# Derby_EDA.net
KiCad netlist of a schematic drawn in EasyEDA
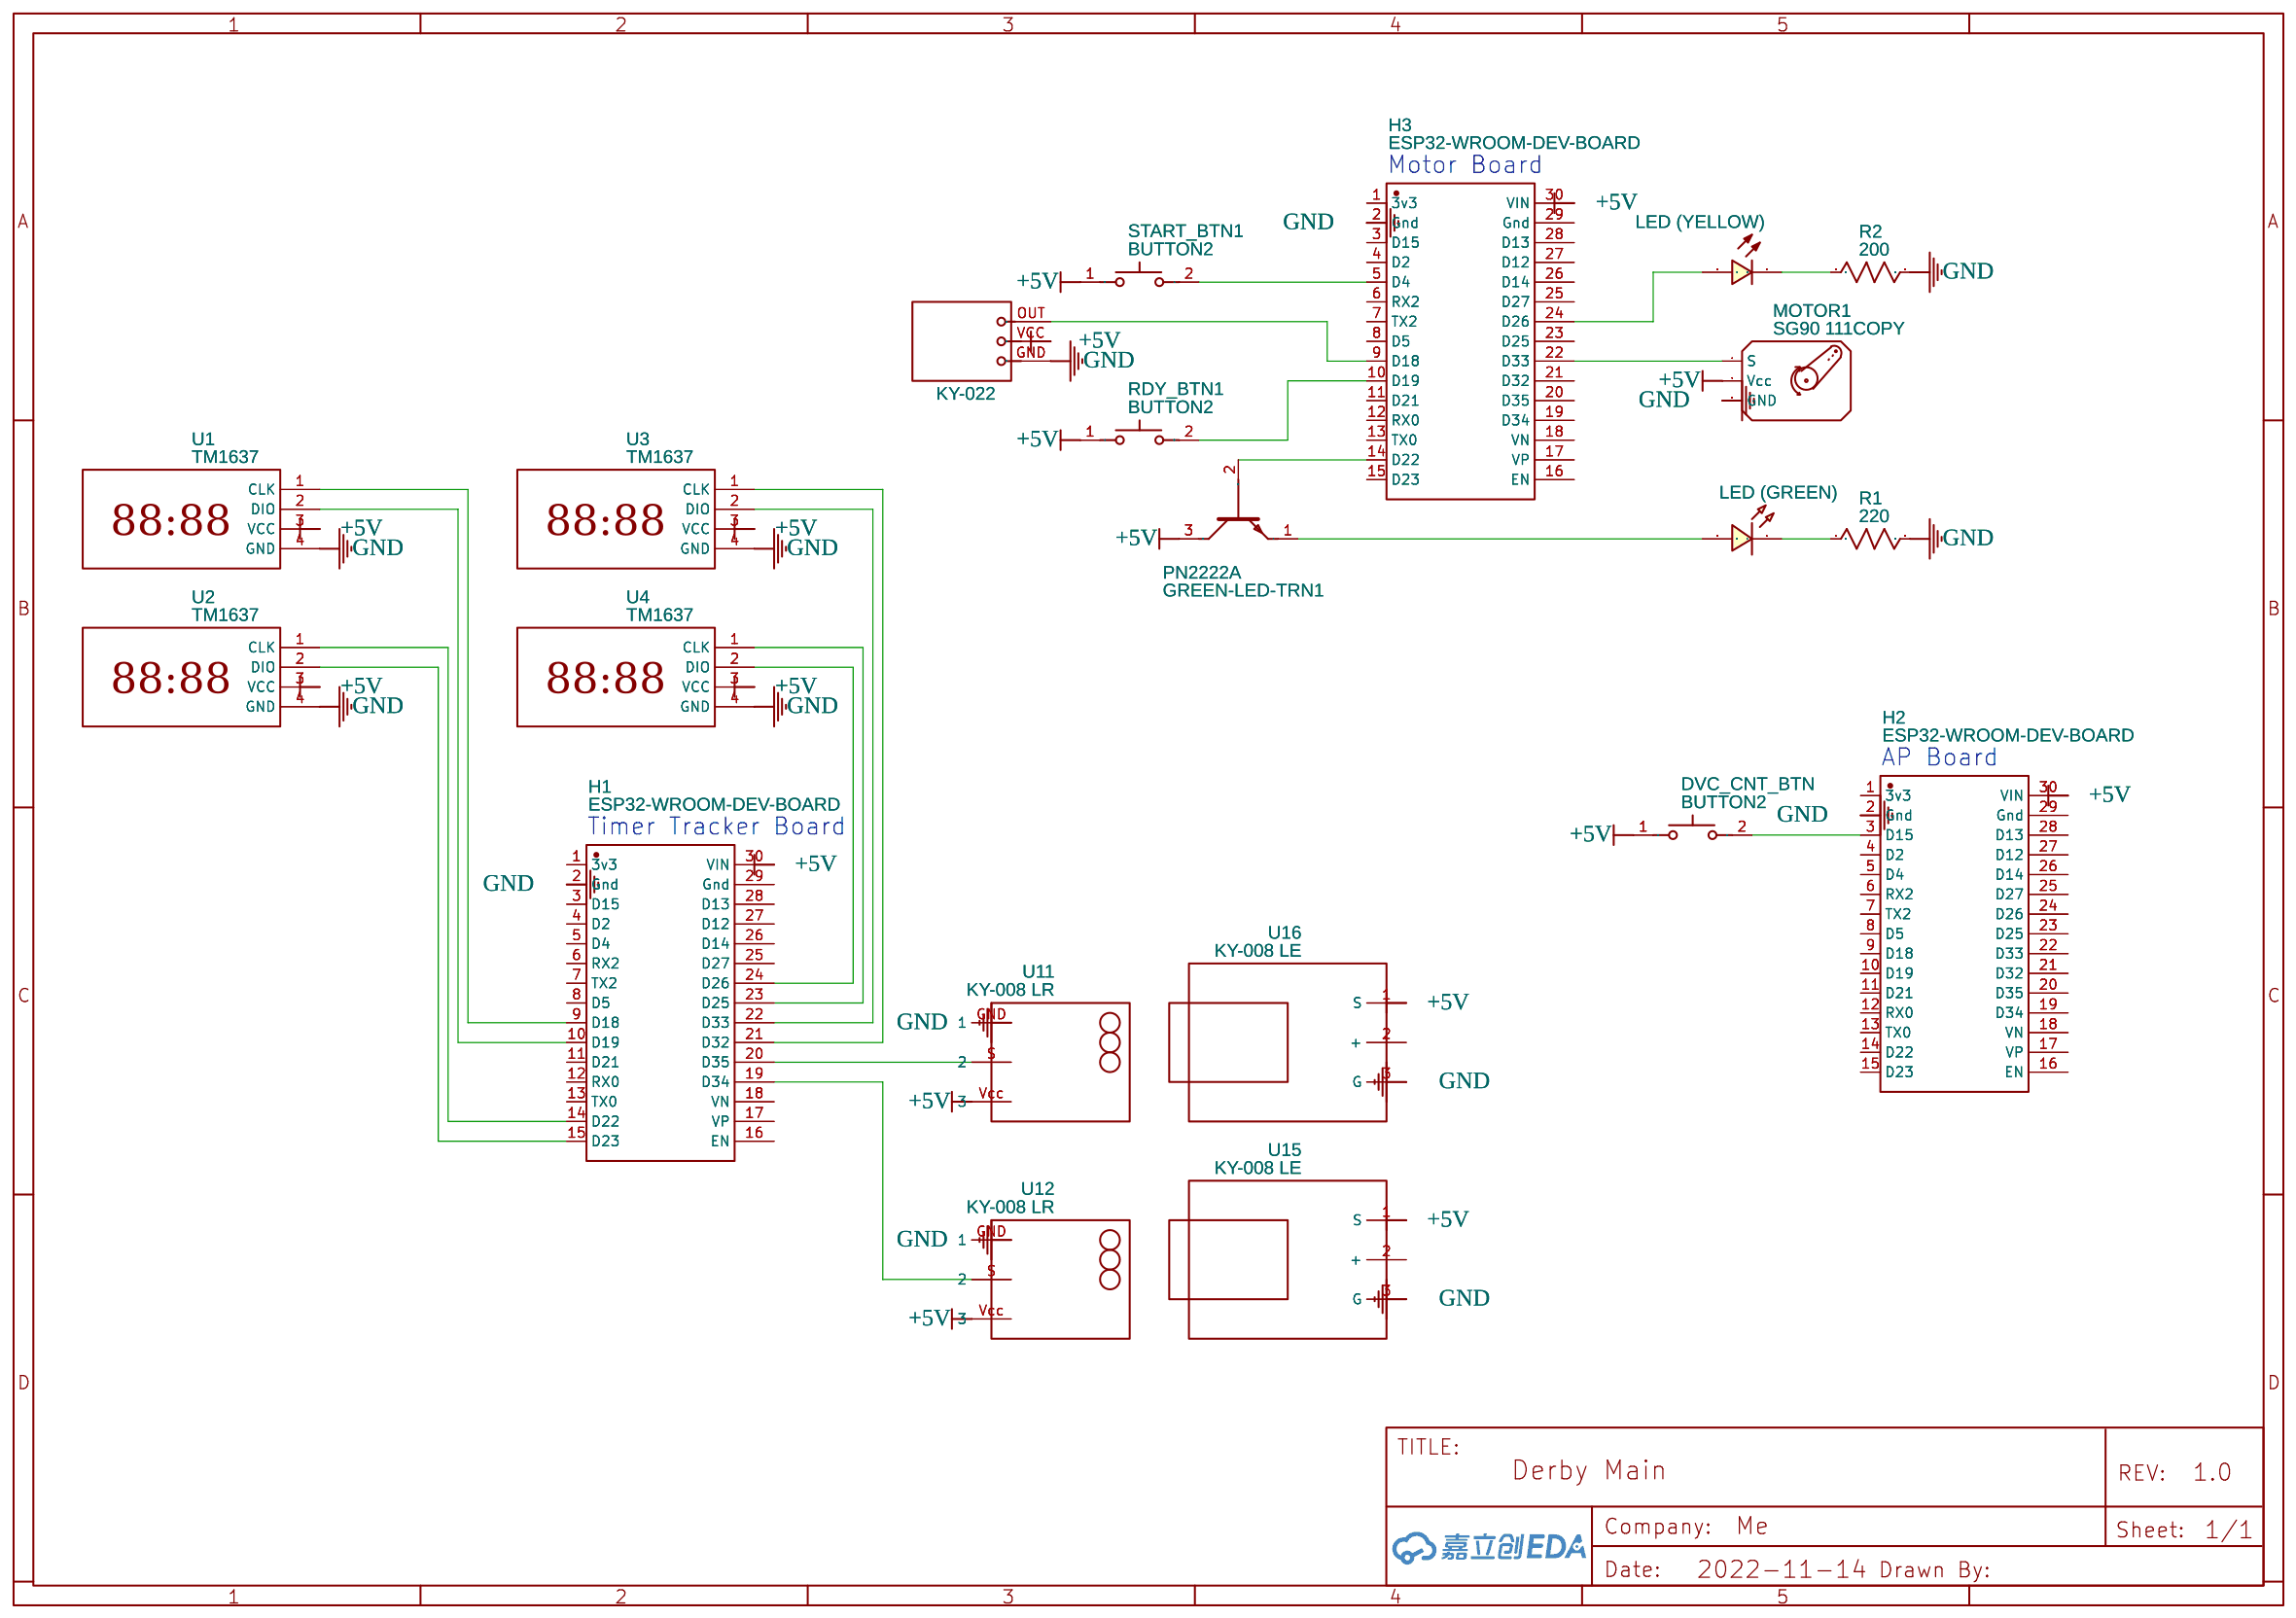
[diagram p0: schematic sheet]

(export (version "E")
  (design (tool "Eeschema 10.0.6"))
  (components
    (comp (ref "DVC_CNT_BTN")
      (value "BUTTON2")
      (fields (field (name "BOM_Supplier Part") "C9900005988"))
      (libsource (lib "") (part "BUTTON2_1"))
    )
    (comp (ref "GREEN-LED-TRN1") (value "PN2222A") (libsource (lib "") (part "PN2222A")))
    (comp (ref "H1")
      (value "ESP32-WROOM-DEV-BOARD")
      (fields
        (field (name "BOM_Manufacturer Part") "ESP32-WROOM-DEV")
        (field (name "BOM_Supplier Part") "ESP32")
      )
      (libsource (lib "") (part "ESP32-WROOM-DEV-BOARD"))
    )
    (comp (ref "H2")
      (value "ESP32-WROOM-DEV-BOARD")
      (fields
        (field (name "BOM_Manufacturer Part") "ESP32-WROOM-DEV")
        (field (name "BOM_Supplier Part") "ESP32")
      )
      (libsource (lib "") (part "ESP32-WROOM-DEV-BOARD"))
    )
    (comp (ref "H3")
      (value "ESP32-WROOM-DEV-BOARD")
      (fields
        (field (name "BOM_Manufacturer Part") "ESP32-WROOM-DEV")
        (field (name "BOM_Supplier Part") "ESP32")
      )
      (libsource (lib "") (part "ESP32-WROOM-DEV-BOARD"))
    )
    (comp (ref "LED1")
      (value "LED (GREEN)")
      (fields
        (field (name "BOM_Manufacturer Part") "LED三色(Red,Yellow,Green)")
        (field (name "BOM_Supplier Part") "C9900027004")
      )
      (libsource (lib "") (part "LED (GREEN)"))
    )
    (comp (ref "LED2")
      (value "LED (YELLOW)")
      (fields
        (field (name "BOM_Manufacturer Part") "19-213/Y2C-CQ1R1L/3T")
        (field (name "BOM_Supplier Part") "C264455")
      )
      (libsource (lib "") (part "Yellow LED"))
    )
    (comp (ref "MOTOR1") (value "SG90 111COPY") (libsource (lib "") (part "SG90 111COPY")))
    (comp (ref "R1") (value "220") (libsource (lib "") (part "R_AXIAL-0.6_US")))
    (comp (ref "R2") (value "200") (libsource (lib "") (part "R_AXIAL-0.6_US")))
    (comp (ref "RDY_BTN1")
      (value "BUTTON2")
      (fields (field (name "BOM_Supplier Part") "C9900005988"))
      (libsource (lib "") (part "BUTTON2_2"))
    )
    (comp (ref "START_BTN1")
      (value "BUTTON2")
      (fields (field (name "BOM_Supplier Part") "C9900005988"))
      (libsource (lib "") (part "BUTTON2"))
    )
    (comp (ref "U1") (value "TM1637") (libsource (lib "") (part "TM1637")))
    (comp (ref "U2") (value "TM1637") (libsource (lib "") (part "TM1637")))
    (comp (ref "U3") (value "TM1637") (libsource (lib "") (part "TM1637")))
    (comp (ref "U4") (value "TM1637") (libsource (lib "") (part "TM1637")))
    (comp (ref "U5") (value "KY-022") (libsource (lib "") (part "KY-022")))
    (comp (ref "U11")
      (value "KY-008 LR")
      (fields (field (name "BOM_Supplier Part") "KY-008"))
      (libsource (lib "") (part "Laser Receiver (KY-008)"))
    )
    (comp (ref "U12")
      (value "KY-008 LR")
      (fields (field (name "BOM_Supplier Part") "KY-008"))
      (libsource (lib "") (part "Laser Receiver (KY-008)"))
    )
    (comp (ref "U15") (value "KY-008 LE") (libsource (lib "") (part "KY-008//")))
    (comp (ref "U16") (value "KY-008 LE") (libsource (lib "") (part "KY-008//")))
  )
  (nets
    (net (code "1") (name "+5V") (class "Default")
      (node (ref "DVC_CNT_BTN") (pin "1") (pinfunction "1_1") (pintype "unspecified"))
      (node (ref "GREEN-LED-TRN1") (pin "3") (pinfunction "C_3") (pintype "bidirectional"))
      (node (ref "H1") (pin "30") (pinfunction "VIN_30") (pintype "unspecified"))
      (node (ref "H2") (pin "30") (pinfunction "VIN_30") (pintype "unspecified"))
      (node (ref "H3") (pin "30") (pinfunction "VIN_30") (pintype "unspecified"))
      (node (ref "MOTOR1") (pin "2") (pinfunction "Vcc_2") (pintype "unspecified"))
      (node (ref "RDY_BTN1") (pin "1") (pinfunction "1_1") (pintype "unspecified"))
      (node (ref "START_BTN1") (pin "1") (pinfunction "1_1") (pintype "unspecified"))
      (node (ref "U1") (pin "3") (pinfunction "VCC_3") (pintype "unspecified"))
      (node (ref "U15") (pin "1") (pinfunction "S_1") (pintype "unspecified"))
      (node (ref "U16") (pin "1") (pinfunction "S_1") (pintype "unspecified"))
      (node (ref "U2") (pin "3") (pinfunction "VCC_3") (pintype "unspecified"))
      (node (ref "U3") (pin "3") (pinfunction "VCC_3") (pintype "unspecified"))
      (node (ref "U4") (pin "3") (pinfunction "VCC_3") (pintype "unspecified"))
      (node (ref "U5") (pin "VCC") (pinfunction "2_VCC") (pintype "unspecified"))
    )
    (net (code "2") (name "GND") (class "Default")
      (node (ref "H1") (pin "2") (pinfunction "Gnd_2") (pintype "unspecified"))
      (node (ref "H2") (pin "2") (pinfunction "Gnd_2") (pintype "unspecified"))
      (node (ref "H3") (pin "2") (pinfunction "Gnd_2") (pintype "unspecified"))
      (node (ref "MOTOR1") (pin "3") (pinfunction "GND_3") (pintype "unspecified"))
      (node (ref "R1") (pin "2") (pinfunction "2_2") (pintype "unspecified"))
      (node (ref "R2") (pin "2") (pinfunction "2_2") (pintype "unspecified"))
      (node (ref "U1") (pin "4") (pinfunction "GND_4") (pintype "unspecified"))
      (node (ref "U11") (pin "GND") (pinfunction "1_GND") (pintype "unspecified"))
      (node (ref "U12") (pin "GND") (pinfunction "1_GND") (pintype "unspecified"))
      (node (ref "U15") (pin "3") (pinfunction "G_3") (pintype "unspecified"))
      (node (ref "U16") (pin "3") (pinfunction "G_3") (pintype "unspecified"))
      (node (ref "U2") (pin "4") (pinfunction "GND_4") (pintype "unspecified"))
      (node (ref "U3") (pin "4") (pinfunction "GND_4") (pintype "unspecified"))
      (node (ref "U4") (pin "4") (pinfunction "GND_4") (pintype "unspecified"))
      (node (ref "U5") (pin "GND") (pinfunction "1_GND") (pintype "unspecified"))
    )
    (net (code "3") (name "Net-(GREEN-LED-TRN1-B)") (class "Default")
      (node (ref "GREEN-LED-TRN1") (pin "2") (pinfunction "B_2") (pintype "bidirectional"))
      (node (ref "H3") (pin "14") (pinfunction "D22_14") (pintype "unspecified"))
    )
    (net (code "4") (name "Net-(GREEN-LED-TRN1-E)") (class "Default")
      (node (ref "GREEN-LED-TRN1") (pin "1") (pinfunction "E_1") (pintype "bidirectional"))
      (node (ref "LED1") (pin "2") (pinfunction "2_2") (pintype "unspecified"))
    )
    (net (code "5") (name "Net-(H1-D18)") (class "Default")
      (node (ref "H1") (pin "9") (pinfunction "D18_9") (pintype "unspecified"))
      (node (ref "U1") (pin "1") (pinfunction "CLK_1") (pintype "unspecified"))
    )
    (net (code "6") (name "Net-(H1-D19)") (class "Default")
      (node (ref "H1") (pin "10") (pinfunction "D19_10") (pintype "unspecified"))
      (node (ref "U1") (pin "2") (pinfunction "DIO_2") (pintype "unspecified"))
    )
    (net (code "7") (name "Net-(H1-D22)") (class "Default")
      (node (ref "H1") (pin "14") (pinfunction "D22_14") (pintype "unspecified"))
      (node (ref "U2") (pin "1") (pinfunction "CLK_1") (pintype "unspecified"))
    )
    (net (code "8") (name "Net-(H1-D23)") (class "Default")
      (node (ref "H1") (pin "15") (pinfunction "D23_15") (pintype "unspecified"))
      (node (ref "U2") (pin "2") (pinfunction "DIO_2") (pintype "unspecified"))
    )
    (net (code "9") (name "Net-(H1-D25)") (class "Default")
      (node (ref "H1") (pin "23") (pinfunction "D25_23") (pintype "unspecified"))
      (node (ref "U4") (pin "1") (pinfunction "CLK_1") (pintype "unspecified"))
    )
    (net (code "10") (name "Net-(H1-D26)") (class "Default")
      (node (ref "H1") (pin "24") (pinfunction "D26_24") (pintype "unspecified"))
      (node (ref "U4") (pin "2") (pinfunction "DIO_2") (pintype "unspecified"))
    )
    (net (code "11") (name "Net-(H1-D32)") (class "Default")
      (node (ref "H1") (pin "21") (pinfunction "D32_21") (pintype "unspecified"))
      (node (ref "U3") (pin "1") (pinfunction "CLK_1") (pintype "unspecified"))
    )
    (net (code "12") (name "Net-(H1-D33)") (class "Default")
      (node (ref "H1") (pin "22") (pinfunction "D33_22") (pintype "unspecified"))
      (node (ref "U3") (pin "2") (pinfunction "DIO_2") (pintype "unspecified"))
    )
    (net (code "13") (name "Net-(H1-D34)") (class "Default")
      (node (ref "H1") (pin "19") (pinfunction "D34_19") (pintype "unspecified"))
      (node (ref "U12") (pin "S") (pinfunction "2_S") (pintype "unspecified"))
    )
    (net (code "14") (name "Net-(H1-D35)") (class "Default")
      (node (ref "H1") (pin "20") (pinfunction "D35_20") (pintype "unspecified"))
      (node (ref "U11") (pin "S") (pinfunction "2_S") (pintype "unspecified"))
    )
    (net (code "15") (name "Net-(H2-D15)") (class "Default")
      (node (ref "DVC_CNT_BTN") (pin "2") (pinfunction "2_2") (pintype "unspecified"))
      (node (ref "H2") (pin "3") (pinfunction "D15_3") (pintype "unspecified"))
    )
    (net (code "16") (name "Net-(H3-D4)") (class "Default")
      (node (ref "H3") (pin "5") (pinfunction "D4_5") (pintype "unspecified"))
      (node (ref "START_BTN1") (pin "2") (pinfunction "2_2") (pintype "unspecified"))
    )
    (net (code "17") (name "Net-(H3-D18)") (class "Default")
      (node (ref "H3") (pin "9") (pinfunction "D18_9") (pintype "unspecified"))
      (node (ref "U5") (pin "OUT") (pinfunction "3_OUT") (pintype "unspecified"))
    )
    (net (code "18") (name "Net-(H3-D19)") (class "Default")
      (node (ref "H3") (pin "10") (pinfunction "D19_10") (pintype "unspecified"))
      (node (ref "RDY_BTN1") (pin "2") (pinfunction "2_2") (pintype "unspecified"))
    )
    (net (code "19") (name "Net-(H3-D26)") (class "Default")
      (node (ref "H3") (pin "24") (pinfunction "D26_24") (pintype "unspecified"))
      (node (ref "LED2") (pin "2") (pinfunction "A_2") (pintype "input"))
    )
    (net (code "20") (name "Net-(H3-D33)") (class "Default")
      (node (ref "H3") (pin "22") (pinfunction "D33_22") (pintype "unspecified"))
      (node (ref "MOTOR1") (pin "1") (pinfunction "S_1") (pintype "unspecified"))
    )
    (net (code "21") (name "Net-(LED1-Pad1)") (class "Default")
      (node (ref "LED1") (pin "1") (pinfunction "1_1") (pintype "unspecified"))
      (node (ref "R1") (pin "1") (pinfunction "1_1") (pintype "unspecified"))
    )
    (net (code "22") (name "Net-(LED2-C)") (class "Default")
      (node (ref "LED2") (pin "1") (pinfunction "C_1") (pintype "input"))
      (node (ref "R2") (pin "1") (pinfunction "1_1") (pintype "unspecified"))
    )
    (net (code "23") (name "unconnected-(H1-3v3-Pad1)") (class "Default")
      (node (ref "H1") (pin "1") (pinfunction "3v3_1") (pintype "unspecified"))
    )
    (net (code "24") (name "unconnected-(H1-D2-Pad4)") (class "Default")
      (node (ref "H1") (pin "4") (pinfunction "D2_4") (pintype "unspecified"))
    )
    (net (code "25") (name "unconnected-(H1-D4-Pad5)") (class "Default")
      (node (ref "H1") (pin "5") (pinfunction "D4_5") (pintype "unspecified"))
    )
    (net (code "26") (name "unconnected-(H1-D5-Pad8)") (class "Default")
      (node (ref "H1") (pin "8") (pinfunction "D5_8") (pintype "unspecified"))
    )
    (net (code "27") (name "unconnected-(H1-D12-Pad27)") (class "Default")
      (node (ref "H1") (pin "27") (pinfunction "D12_27") (pintype "unspecified"))
    )
    (net (code "28") (name "unconnected-(H1-D13-Pad28)") (class "Default")
      (node (ref "H1") (pin "28") (pinfunction "D13_28") (pintype "unspecified"))
    )
    (net (code "29") (name "unconnected-(H1-D14-Pad26)") (class "Default")
      (node (ref "H1") (pin "26") (pinfunction "D14_26") (pintype "unspecified"))
    )
    (net (code "30") (name "unconnected-(H1-D15-Pad3)") (class "Default")
      (node (ref "H1") (pin "3") (pinfunction "D15_3") (pintype "unspecified"))
    )
    (net (code "31") (name "unconnected-(H1-D21-Pad11)") (class "Default")
      (node (ref "H1") (pin "11") (pinfunction "D21_11") (pintype "unspecified"))
    )
    (net (code "32") (name "unconnected-(H1-D27-Pad25)") (class "Default")
      (node (ref "H1") (pin "25") (pinfunction "D27_25") (pintype "unspecified"))
    )
    (net (code "33") (name "unconnected-(H1-EN-Pad16)") (class "Default")
      (node (ref "H1") (pin "16") (pinfunction "EN_16") (pintype "unspecified"))
    )
    (net (code "34") (name "unconnected-(H1-Gnd-Pad29)") (class "Default")
      (node (ref "H1") (pin "29") (pinfunction "Gnd_29") (pintype "unspecified"))
    )
    (net (code "35") (name "unconnected-(H1-RX0-Pad12)") (class "Default")
      (node (ref "H1") (pin "12") (pinfunction "RX0_12") (pintype "unspecified"))
    )
    (net (code "36") (name "unconnected-(H1-RX2-Pad6)") (class "Default")
      (node (ref "H1") (pin "6") (pinfunction "RX2_6") (pintype "unspecified"))
    )
    (net (code "37") (name "unconnected-(H1-TX0-Pad13)") (class "Default")
      (node (ref "H1") (pin "13") (pinfunction "TX0_13") (pintype "unspecified"))
    )
    (net (code "38") (name "unconnected-(H1-TX2-Pad7)") (class "Default")
      (node (ref "H1") (pin "7") (pinfunction "TX2_7") (pintype "unspecified"))
    )
    (net (code "39") (name "unconnected-(H1-VN-Pad18)") (class "Default")
      (node (ref "H1") (pin "18") (pinfunction "VN_18") (pintype "unspecified"))
    )
    (net (code "40") (name "unconnected-(H1-VP-Pad17)") (class "Default")
      (node (ref "H1") (pin "17") (pinfunction "VP_17") (pintype "unspecified"))
    )
    (net (code "41") (name "unconnected-(H2-3v3-Pad1)") (class "Default")
      (node (ref "H2") (pin "1") (pinfunction "3v3_1") (pintype "unspecified"))
    )
    (net (code "42") (name "unconnected-(H2-D2-Pad4)") (class "Default")
      (node (ref "H2") (pin "4") (pinfunction "D2_4") (pintype "unspecified"))
    )
    (net (code "43") (name "unconnected-(H2-D4-Pad5)") (class "Default")
      (node (ref "H2") (pin "5") (pinfunction "D4_5") (pintype "unspecified"))
    )
    (net (code "44") (name "unconnected-(H2-D5-Pad8)") (class "Default")
      (node (ref "H2") (pin "8") (pinfunction "D5_8") (pintype "unspecified"))
    )
    (net (code "45") (name "unconnected-(H2-D12-Pad27)") (class "Default")
      (node (ref "H2") (pin "27") (pinfunction "D12_27") (pintype "unspecified"))
    )
    (net (code "46") (name "unconnected-(H2-D13-Pad28)") (class "Default")
      (node (ref "H2") (pin "28") (pinfunction "D13_28") (pintype "unspecified"))
    )
    (net (code "47") (name "unconnected-(H2-D14-Pad26)") (class "Default")
      (node (ref "H2") (pin "26") (pinfunction "D14_26") (pintype "unspecified"))
    )
    (net (code "48") (name "unconnected-(H2-D18-Pad9)") (class "Default")
      (node (ref "H2") (pin "9") (pinfunction "D18_9") (pintype "unspecified"))
    )
    (net (code "49") (name "unconnected-(H2-D19-Pad10)") (class "Default")
      (node (ref "H2") (pin "10") (pinfunction "D19_10") (pintype "unspecified"))
    )
    (net (code "50") (name "unconnected-(H2-D21-Pad11)") (class "Default")
      (node (ref "H2") (pin "11") (pinfunction "D21_11") (pintype "unspecified"))
    )
    (net (code "51") (name "unconnected-(H2-D22-Pad14)") (class "Default")
      (node (ref "H2") (pin "14") (pinfunction "D22_14") (pintype "unspecified"))
    )
    (net (code "52") (name "unconnected-(H2-D23-Pad15)") (class "Default")
      (node (ref "H2") (pin "15") (pinfunction "D23_15") (pintype "unspecified"))
    )
    (net (code "53") (name "unconnected-(H2-D25-Pad23)") (class "Default")
      (node (ref "H2") (pin "23") (pinfunction "D25_23") (pintype "unspecified"))
    )
    (net (code "54") (name "unconnected-(H2-D26-Pad24)") (class "Default")
      (node (ref "H2") (pin "24") (pinfunction "D26_24") (pintype "unspecified"))
    )
    (net (code "55") (name "unconnected-(H2-D27-Pad25)") (class "Default")
      (node (ref "H2") (pin "25") (pinfunction "D27_25") (pintype "unspecified"))
    )
    (net (code "56") (name "unconnected-(H2-D32-Pad21)") (class "Default")
      (node (ref "H2") (pin "21") (pinfunction "D32_21") (pintype "unspecified"))
    )
    (net (code "57") (name "unconnected-(H2-D33-Pad22)") (class "Default")
      (node (ref "H2") (pin "22") (pinfunction "D33_22") (pintype "unspecified"))
    )
    (net (code "58") (name "unconnected-(H2-D34-Pad19)") (class "Default")
      (node (ref "H2") (pin "19") (pinfunction "D34_19") (pintype "unspecified"))
    )
    (net (code "59") (name "unconnected-(H2-D35-Pad20)") (class "Default")
      (node (ref "H2") (pin "20") (pinfunction "D35_20") (pintype "unspecified"))
    )
    (net (code "60") (name "unconnected-(H2-EN-Pad16)") (class "Default")
      (node (ref "H2") (pin "16") (pinfunction "EN_16") (pintype "unspecified"))
    )
    (net (code "61") (name "unconnected-(H2-Gnd-Pad29)") (class "Default")
      (node (ref "H2") (pin "29") (pinfunction "Gnd_29") (pintype "unspecified"))
    )
    (net (code "62") (name "unconnected-(H2-RX0-Pad12)") (class "Default")
      (node (ref "H2") (pin "12") (pinfunction "RX0_12") (pintype "unspecified"))
    )
    (net (code "63") (name "unconnected-(H2-RX2-Pad6)") (class "Default")
      (node (ref "H2") (pin "6") (pinfunction "RX2_6") (pintype "unspecified"))
    )
    (net (code "64") (name "unconnected-(H2-TX0-Pad13)") (class "Default")
      (node (ref "H2") (pin "13") (pinfunction "TX0_13") (pintype "unspecified"))
    )
    (net (code "65") (name "unconnected-(H2-TX2-Pad7)") (class "Default")
      (node (ref "H2") (pin "7") (pinfunction "TX2_7") (pintype "unspecified"))
    )
    (net (code "66") (name "unconnected-(H2-VN-Pad18)") (class "Default")
      (node (ref "H2") (pin "18") (pinfunction "VN_18") (pintype "unspecified"))
    )
    (net (code "67") (name "unconnected-(H2-VP-Pad17)") (class "Default")
      (node (ref "H2") (pin "17") (pinfunction "VP_17") (pintype "unspecified"))
    )
    (net (code "68") (name "unconnected-(H3-3v3-Pad1)") (class "Default")
      (node (ref "H3") (pin "1") (pinfunction "3v3_1") (pintype "unspecified"))
    )
    (net (code "69") (name "unconnected-(H3-D2-Pad4)") (class "Default")
      (node (ref "H3") (pin "4") (pinfunction "D2_4") (pintype "unspecified"))
    )
    (net (code "70") (name "unconnected-(H3-D5-Pad8)") (class "Default")
      (node (ref "H3") (pin "8") (pinfunction "D5_8") (pintype "unspecified"))
    )
    (net (code "71") (name "unconnected-(H3-D12-Pad27)") (class "Default")
      (node (ref "H3") (pin "27") (pinfunction "D12_27") (pintype "unspecified"))
    )
    (net (code "72") (name "unconnected-(H3-D13-Pad28)") (class "Default")
      (node (ref "H3") (pin "28") (pinfunction "D13_28") (pintype "unspecified"))
    )
    (net (code "73") (name "unconnected-(H3-D14-Pad26)") (class "Default")
      (node (ref "H3") (pin "26") (pinfunction "D14_26") (pintype "unspecified"))
    )
    (net (code "74") (name "unconnected-(H3-D15-Pad3)") (class "Default")
      (node (ref "H3") (pin "3") (pinfunction "D15_3") (pintype "unspecified"))
    )
    (net (code "75") (name "unconnected-(H3-D21-Pad11)") (class "Default")
      (node (ref "H3") (pin "11") (pinfunction "D21_11") (pintype "unspecified"))
    )
    (net (code "76") (name "unconnected-(H3-D23-Pad15)") (class "Default")
      (node (ref "H3") (pin "15") (pinfunction "D23_15") (pintype "unspecified"))
    )
    (net (code "77") (name "unconnected-(H3-D25-Pad23)") (class "Default")
      (node (ref "H3") (pin "23") (pinfunction "D25_23") (pintype "unspecified"))
    )
    (net (code "78") (name "unconnected-(H3-D27-Pad25)") (class "Default")
      (node (ref "H3") (pin "25") (pinfunction "D27_25") (pintype "unspecified"))
    )
    (net (code "79") (name "unconnected-(H3-D32-Pad21)") (class "Default")
      (node (ref "H3") (pin "21") (pinfunction "D32_21") (pintype "unspecified"))
    )
    (net (code "80") (name "unconnected-(H3-D34-Pad19)") (class "Default")
      (node (ref "H3") (pin "19") (pinfunction "D34_19") (pintype "unspecified"))
    )
    (net (code "81") (name "unconnected-(H3-D35-Pad20)") (class "Default")
      (node (ref "H3") (pin "20") (pinfunction "D35_20") (pintype "unspecified"))
    )
    (net (code "82") (name "unconnected-(H3-EN-Pad16)") (class "Default")
      (node (ref "H3") (pin "16") (pinfunction "EN_16") (pintype "unspecified"))
    )
    (net (code "83") (name "unconnected-(H3-Gnd-Pad29)") (class "Default")
      (node (ref "H3") (pin "29") (pinfunction "Gnd_29") (pintype "unspecified"))
    )
    (net (code "84") (name "unconnected-(H3-RX0-Pad12)") (class "Default")
      (node (ref "H3") (pin "12") (pinfunction "RX0_12") (pintype "unspecified"))
    )
    (net (code "85") (name "unconnected-(H3-RX2-Pad6)") (class "Default")
      (node (ref "H3") (pin "6") (pinfunction "RX2_6") (pintype "unspecified"))
    )
    (net (code "86") (name "unconnected-(H3-TX0-Pad13)") (class "Default")
      (node (ref "H3") (pin "13") (pinfunction "TX0_13") (pintype "unspecified"))
    )
    (net (code "87") (name "unconnected-(H3-TX2-Pad7)") (class "Default")
      (node (ref "H3") (pin "7") (pinfunction "TX2_7") (pintype "unspecified"))
    )
    (net (code "88") (name "unconnected-(H3-VN-Pad18)") (class "Default")
      (node (ref "H3") (pin "18") (pinfunction "VN_18") (pintype "unspecified"))
    )
    (net (code "89") (name "unconnected-(H3-VP-Pad17)") (class "Default")
      (node (ref "H3") (pin "17") (pinfunction "VP_17") (pintype "unspecified"))
    )
    (net (code "90") (name "unconnected-(U11-3-PadVcc)") (class "Default")
      (node (ref "U11") (pin "Vcc") (pinfunction "3_Vcc") (pintype "unspecified"))
    )
    (net (code "91") (name "unconnected-(U12-3-PadVcc)") (class "Default")
      (node (ref "U12") (pin "Vcc") (pinfunction "3_Vcc") (pintype "unspecified"))
    )
    (net (code "92") (name "unconnected-(U15-+-Pad2)") (class "Default")
      (node (ref "U15") (pin "2") (pinfunction "+_2") (pintype "unspecified"))
    )
    (net (code "93") (name "unconnected-(U16-+-Pad2)") (class "Default")
      (node (ref "U16") (pin "2") (pinfunction "+_2") (pintype "unspecified"))
    )
  )
)
